# UP-PAR-Adaptor.net
KiCad netlist of a schematic drawn in EAGLE
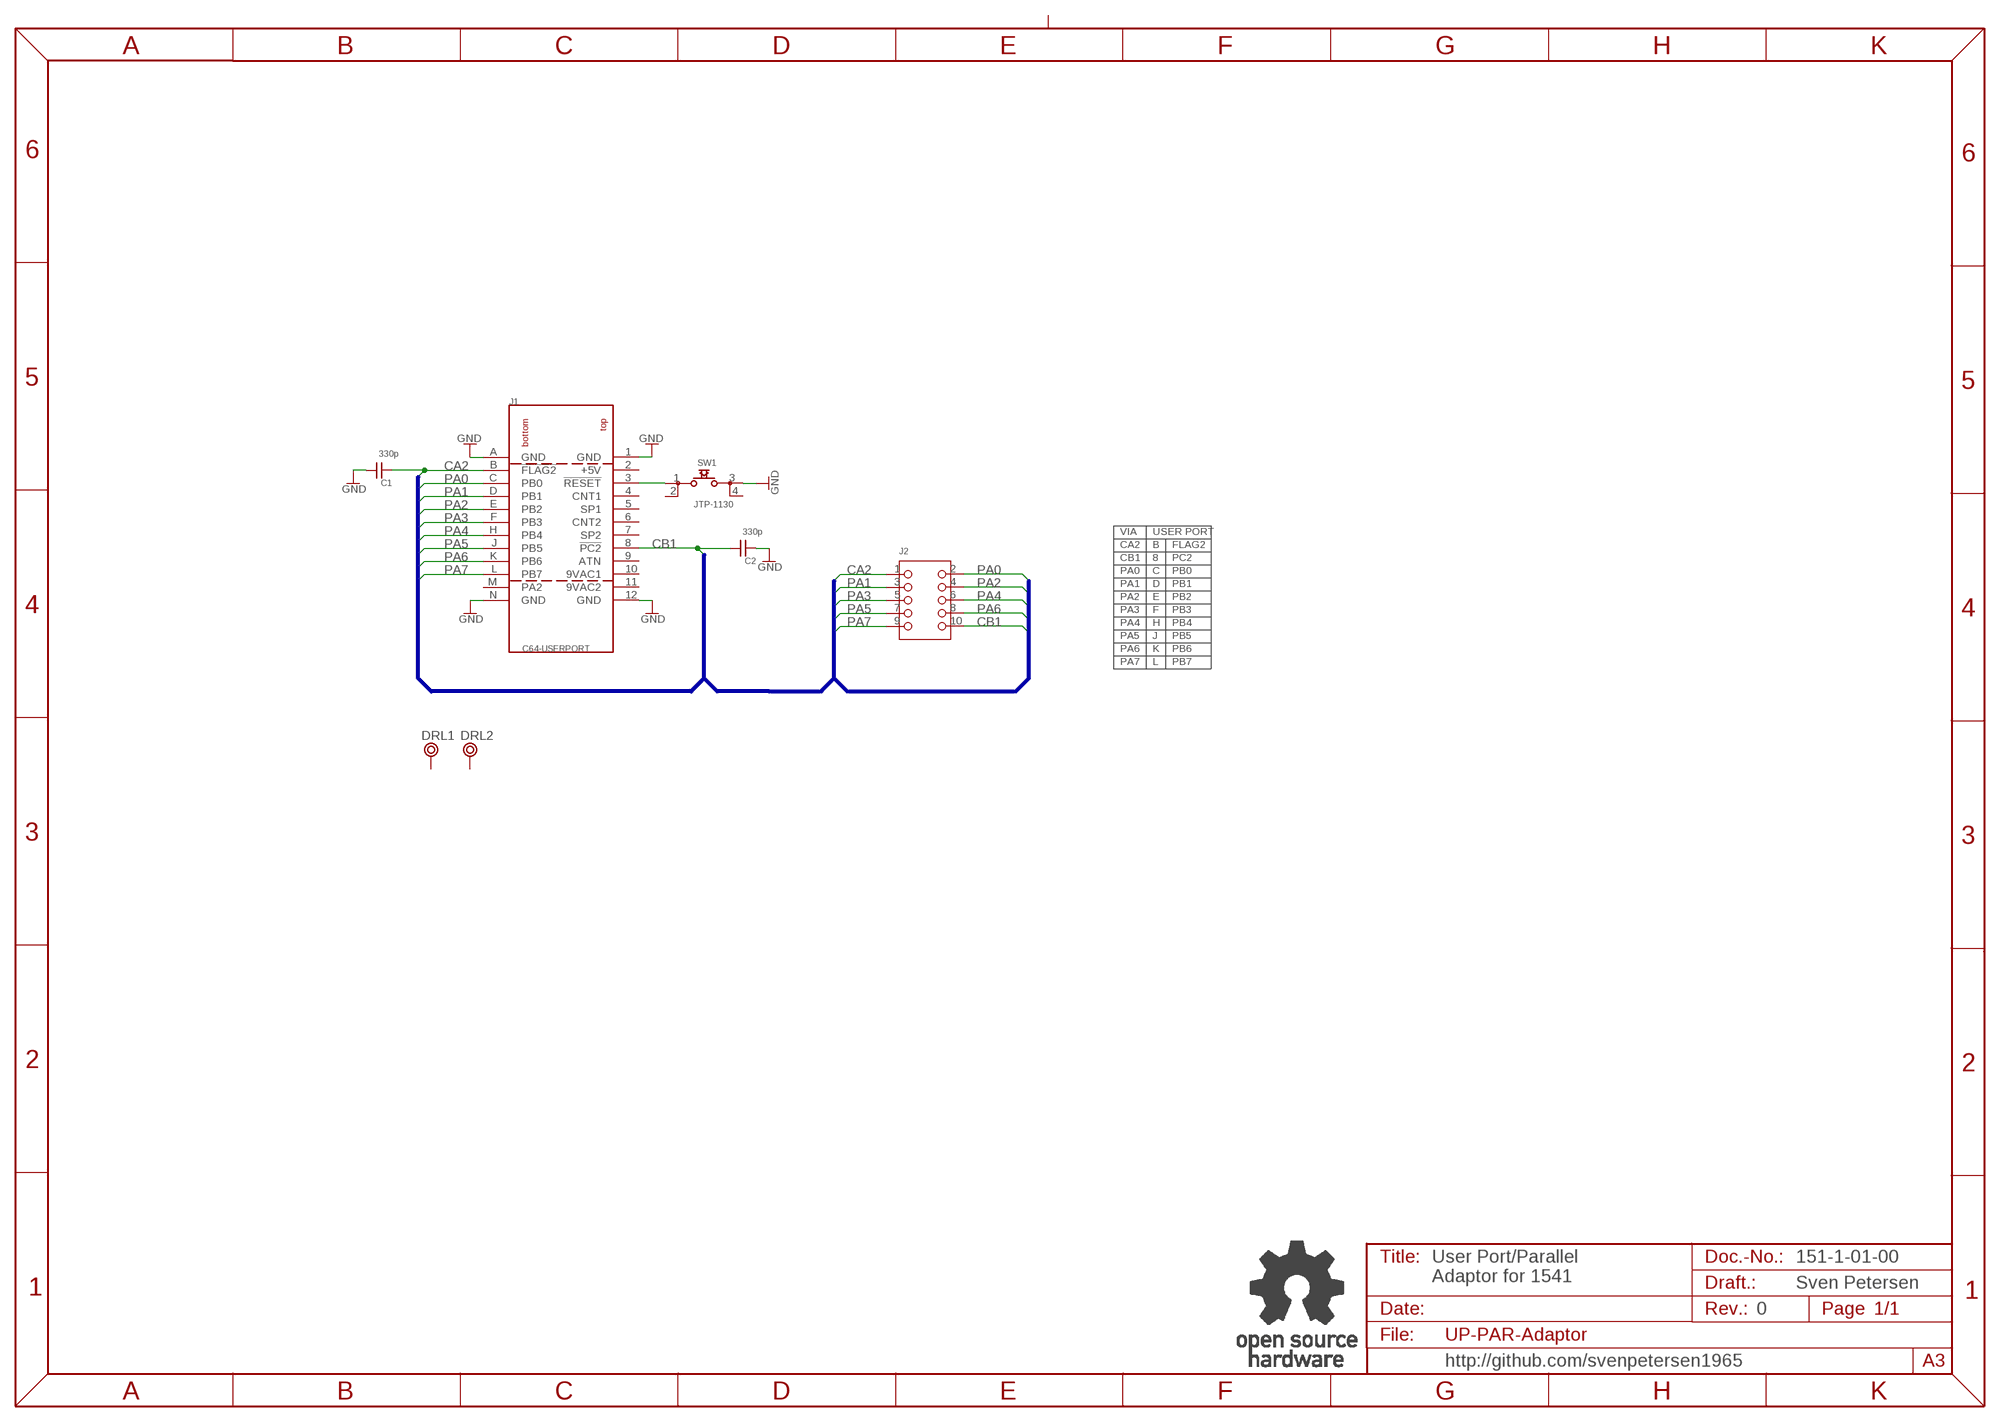
[diagram p0: schematic, sheet 1]

(export (version "E")
  (design (tool "Eeschema 10.0.6"))
  (components
    (comp (ref "C1")
      (value "330p")
      (footprint "eagle-import:C-2,5")
      (libsource (lib "eagle-import") (part "CAP01"))
    )
    (comp (ref "C2")
      (value "330p")
      (footprint "eagle-import:C-2,5")
      (libsource (lib "eagle-import") (part "CAP01"))
    )
    (comp (ref "DRL1")
      (value "BOHR3,5")
      (footprint "eagle-import:BOHR3,5")
      (libsource (lib "eagle-import") (part "BOHR3,5"))
    )
    (comp (ref "DRL2")
      (value "BOHR3,5")
      (footprint "eagle-import:BOHR3,5")
      (libsource (lib "eagle-import") (part "BOHR3,5"))
    )
    (comp (ref "J1")
      (value "C64-USERPORT")
      (footprint "eagle-import:USERPORT")
      (libsource (lib "eagle-import") (part "C64-USERPORT"))
    )
    (comp (ref "J2")
      (value "2X05WV")
      (footprint "eagle-import:2X05WV")
      (libsource (lib "eagle-import") (part "2X05WV"))
    )
    (comp (ref "SW1")
      (value "JTP-1130")
      (footprint "eagle-import:JTP-1130")
      (libsource (lib "eagle-import") (part "JTP-1130"))
    )
    (comp (ref "U$13")
      (value "OPEN_SOURCE_HW")
      (footprint "eagle-import:OPENHW")
      (libsource (lib "eagle-import") (part "OPEN_SOURCE_HW"))
    )
  )
  (nets
    (net (code "1") (name "/+5V") (class "Default")
      (node (ref "J1") (pin "2") (pinfunction "+5V_2") (pintype "power_in"))
    )
    (net (code "2") (name "/9VAC1") (class "Default")
      (node (ref "J1") (pin "10") (pinfunction "9VAC1_10") (pintype "power_in"))
    )
    (net (code "3") (name "/9VAC2") (class "Default")
      (node (ref "J1") (pin "11") (pinfunction "9VAC2_11") (pintype "power_in"))
    )
    (net (code "4") (name "/CA2") (class "Default")
      (node (ref "C1") (pin "1") (pinfunction "1_1") (pintype "passive"))
      (node (ref "J1") (pin "B") (pinfunction "~{FLAG2}_B") (pintype "input"))
      (node (ref "J2") (pin "1") (pinfunction "1_1") (pintype "passive"))
    )
    (net (code "5") (name "/CB1") (class "Default")
      (node (ref "C2") (pin "2") (pinfunction "2_2") (pintype "passive"))
      (node (ref "J1") (pin "8") (pinfunction "~{PC2}_8") (pintype "bidirectional"))
      (node (ref "J2") (pin "10") (pinfunction "10_10") (pintype "passive"))
    )
    (net (code "6") (name "/PA0") (class "Default")
      (node (ref "J1") (pin "C") (pinfunction "PB0_C") (pintype "bidirectional"))
      (node (ref "J2") (pin "2") (pinfunction "2_2") (pintype "passive"))
    )
    (net (code "7") (name "/PA1") (class "Default")
      (node (ref "J1") (pin "D") (pinfunction "PB1_D") (pintype "bidirectional"))
      (node (ref "J2") (pin "3") (pinfunction "3_3") (pintype "passive"))
    )
    (net (code "8") (name "/PA2") (class "Default")
      (node (ref "J1") (pin "E") (pinfunction "PB2_E") (pintype "bidirectional"))
      (node (ref "J2") (pin "4") (pinfunction "4_4") (pintype "passive"))
    )
    (net (code "9") (name "/PA3") (class "Default")
      (node (ref "J1") (pin "F") (pinfunction "PB3_F") (pintype "bidirectional"))
      (node (ref "J2") (pin "5") (pinfunction "5_5") (pintype "passive"))
    )
    (net (code "10") (name "/PA4") (class "Default")
      (node (ref "J1") (pin "H") (pinfunction "PB4_H") (pintype "bidirectional"))
      (node (ref "J2") (pin "6") (pinfunction "6_6") (pintype "passive"))
    )
    (net (code "11") (name "/PA5") (class "Default")
      (node (ref "J1") (pin "J") (pinfunction "PB5_J") (pintype "bidirectional"))
      (node (ref "J2") (pin "7") (pinfunction "7_7") (pintype "passive"))
    )
    (net (code "12") (name "/PA6") (class "Default")
      (node (ref "J1") (pin "K") (pinfunction "PB6_K") (pintype "bidirectional"))
      (node (ref "J2") (pin "8") (pinfunction "8_8") (pintype "passive"))
    )
    (net (code "13") (name "/PA7") (class "Default")
      (node (ref "J1") (pin "L") (pinfunction "PB7_L") (pintype "bidirectional"))
      (node (ref "J2") (pin "9") (pinfunction "9_9") (pintype "passive"))
    )
    (net (code "14") (name "GND") (class "Default")
      (node (ref "C1") (pin "2") (pinfunction "2_2") (pintype "passive"))
      (node (ref "C2") (pin "1") (pinfunction "1_1") (pintype "passive"))
      (node (ref "J1") (pin "1") (pinfunction "GND_1") (pintype "power_in"))
      (node (ref "J1") (pin "12") (pinfunction "GND_12") (pintype "power_in"))
      (node (ref "J1") (pin "A") (pinfunction "GND_A") (pintype "power_in"))
      (node (ref "J1") (pin "N") (pinfunction "GND_N") (pintype "power_in"))
      (node (ref "SW1") (pin "3") (pinfunction "3_3") (pintype "passive"))
    )
    (net (code "15") (name "Net-(J1-~{RESET})") (class "Default")
      (node (ref "J1") (pin "3") (pinfunction "~{RESET}_3") (pintype "bidirectional"))
      (node (ref "SW1") (pin "1") (pinfunction "1_1") (pintype "passive"))
    )
    (net (code "16") (name "unconnected-(DRL1-PadP$1)") (class "Default")
      (node (ref "DRL1") (pin "P$1") (pinfunction "P$1_P$1") (pintype "passive"))
    )
    (net (code "17") (name "unconnected-(DRL2-PadP$1)") (class "Default")
      (node (ref "DRL2") (pin "P$1") (pinfunction "P$1_P$1") (pintype "passive"))
    )
    (net (code "18") (name "unconnected-(J1-ATN-Pad9)") (class "Default")
      (node (ref "J1") (pin "9") (pinfunction "ATN_9") (pintype "bidirectional"))
    )
    (net (code "19") (name "unconnected-(J1-CNT1-Pad4)") (class "Default")
      (node (ref "J1") (pin "4") (pinfunction "CNT1_4") (pintype "input"))
    )
    (net (code "20") (name "unconnected-(J1-CNT2-Pad6)") (class "Default")
      (node (ref "J1") (pin "6") (pinfunction "CNT2_6") (pintype "input"))
    )
    (net (code "21") (name "unconnected-(J1-PA2-PadM)") (class "Default")
      (node (ref "J1") (pin "M") (pinfunction "PA2_M") (pintype "bidirectional"))
    )
    (net (code "22") (name "unconnected-(J1-SP1-Pad5)") (class "Default")
      (node (ref "J1") (pin "5") (pinfunction "SP1_5") (pintype "bidirectional"))
    )
    (net (code "23") (name "unconnected-(J1-SP2-Pad7)") (class "Default")
      (node (ref "J1") (pin "7") (pinfunction "SP2_7") (pintype "bidirectional"))
    )
    (net (code "24") (name "unconnected-(SW1-Pad2)") (class "Default")
      (node (ref "SW1") (pin "2") (pinfunction "2_2") (pintype "passive"))
    )
    (net (code "25") (name "unconnected-(SW1-Pad4)") (class "Default")
      (node (ref "SW1") (pin "4") (pinfunction "4_4") (pintype "passive"))
    )
  )
)
